# Pololu_Magnetic_Encoder.net
KiCad netlist of a schematic drawn in EAGLE
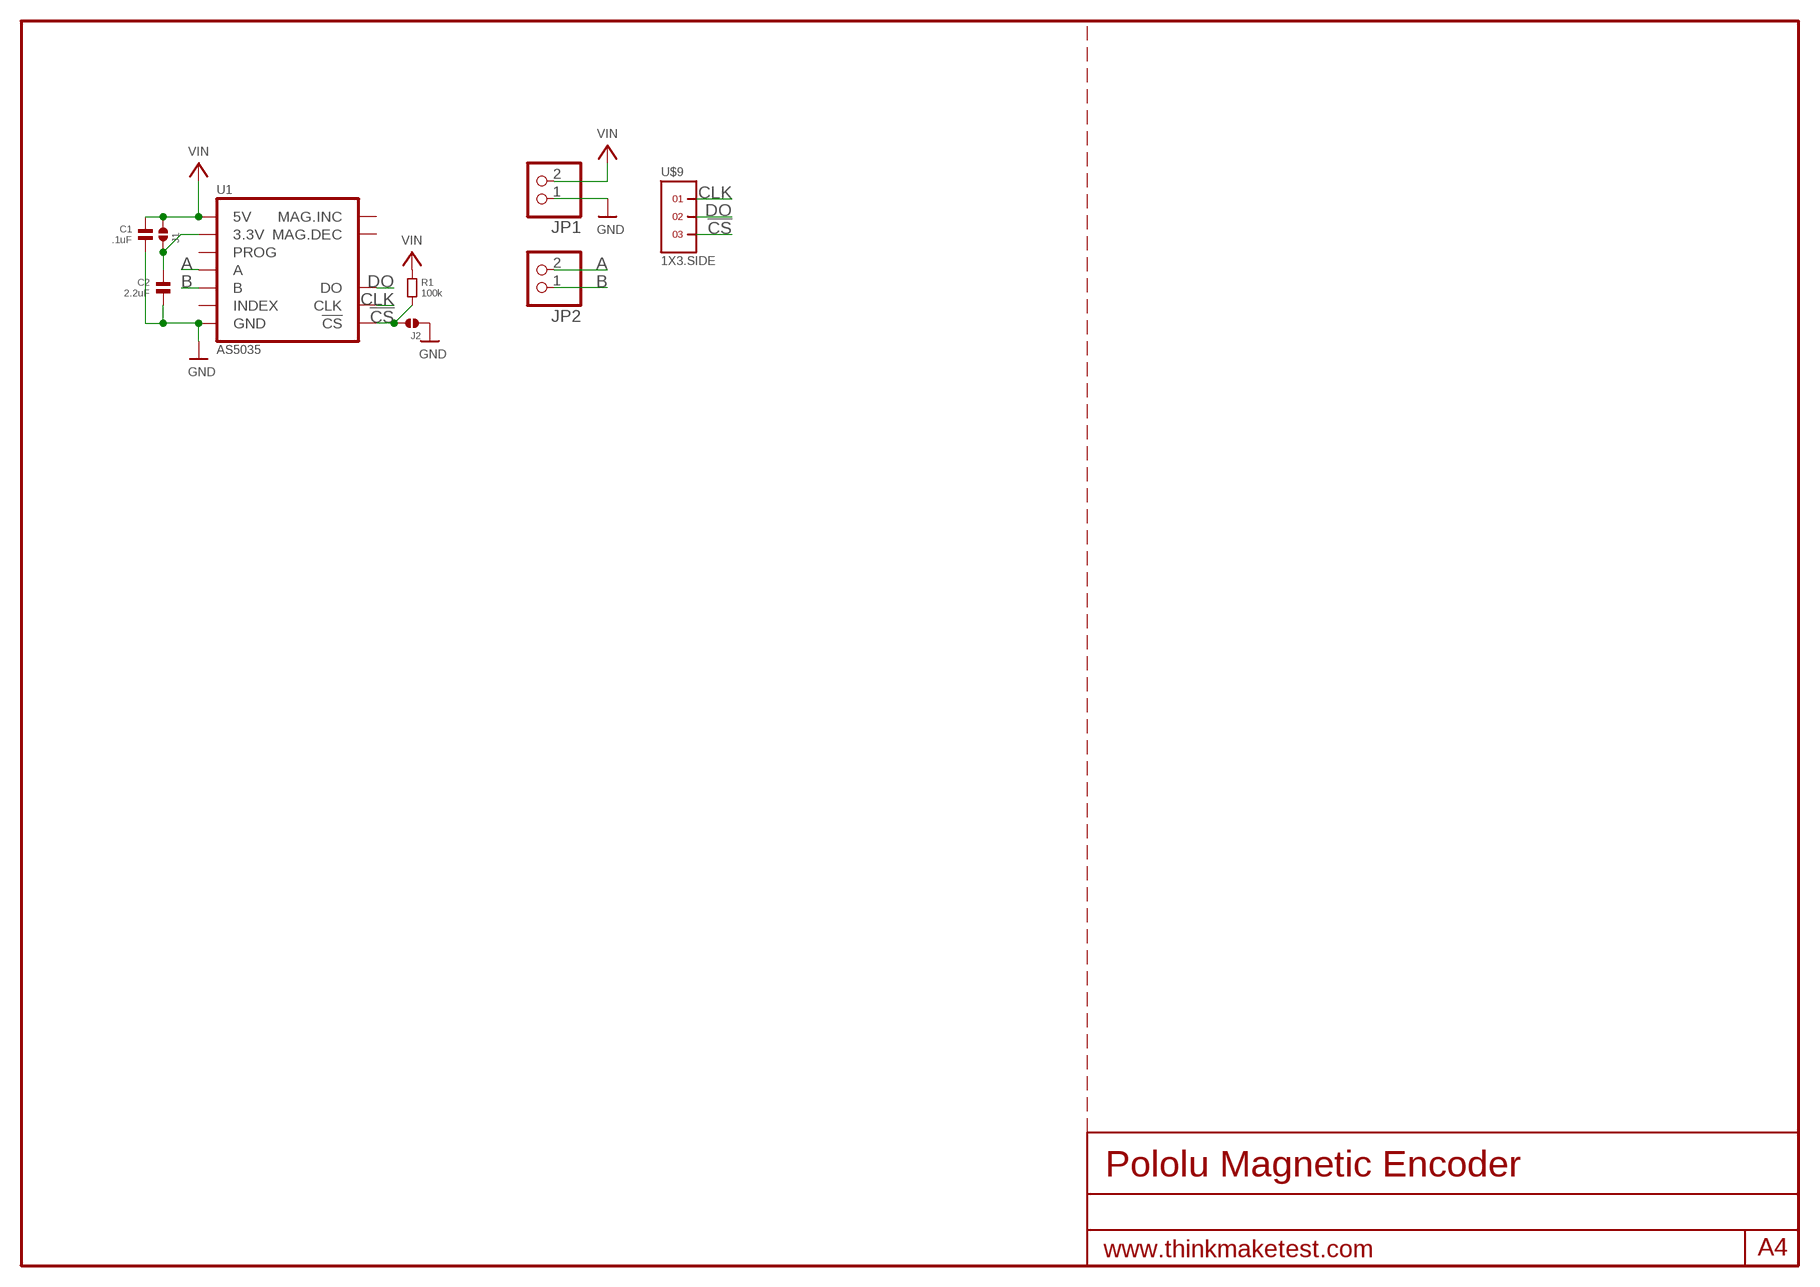
[diagram p0: schematic, sheet 1]

(export (version "E")
  (design (tool "Eeschema 10.0.6"))
  (components
    (comp (ref "C1")
      (value ".1uF")
      (footprint "eagle-import:0603")
      (libsource (lib "eagle-import") (part "CAPACITOR.0603"))
    )
    (comp (ref "C2")
      (value "2.2uF")
      (footprint "eagle-import:0603")
      (libsource (lib "eagle-import") (part "CAPACITOR.0603"))
    )
    (comp (ref "J1")
      (value "SOLDERJUMPER.2.LRG.PASTE")
      (footprint "eagle-import:2.LRG.PASTE")
      (libsource (lib "eagle-import") (part "SOLDERJUMPER.2.LRG.PASTE"))
    )
    (comp (ref "J2")
      (value "SOLDERJUMPER.2.LRG.PASTE")
      (footprint "eagle-import:2.LRG.PASTE")
      (libsource (lib "eagle-import") (part "SOLDERJUMPER.2.LRG.PASTE"))
    )
    (comp (ref "JP1")
      (value "HEADER-1X2ROUND")
      (footprint "eagle-import:1X02_ROUND")
      (libsource (lib "eagle-import") (part "HEADER-1X2ROUND"))
    )
    (comp (ref "JP2")
      (value "HEADER-1X2ROUND")
      (footprint "eagle-import:1X02_ROUND")
      (libsource (lib "eagle-import") (part "HEADER-1X2ROUND"))
    )
    (comp (ref "R1")
      (value "100k")
      (footprint "eagle-import:0603")
      (libsource (lib "eagle-import") (part "RESISTOR.0603"))
    )
    (comp (ref "U$9")
      (value "1X3.SIDE")
      (footprint "eagle-import:1X3.SIDE")
      (libsource (lib "eagle-import") (part "1X3.SIDE"))
    )
    (comp (ref "U1")
      (value "AS5035")
      (footprint "eagle-import:SSOP16")
      (libsource (lib "eagle-import") (part "AS5035"))
    )
  )
  (nets
    (net (code "1") (name "/A") (class "Default")
      (node (ref "JP2") (pin "2") (pinfunction "2_2") (pintype "passive"))
      (node (ref "U1") (pin "3") (pinfunction "A_3") (pintype "bidirectional"))
    )
    (net (code "2") (name "/B") (class "Default")
      (node (ref "JP2") (pin "1") (pinfunction "1_1") (pintype "passive"))
      (node (ref "U1") (pin "4") (pinfunction "B_4") (pintype "bidirectional"))
    )
    (net (code "3") (name "/CLK") (class "Default")
      (node (ref "U$9") (pin "1") (pinfunction "1_1") (pintype "bidirectional"))
      (node (ref "U1") (pin "10") (pinfunction "CLK_10") (pintype "bidirectional"))
    )
    (net (code "4") (name "/DO") (class "Default")
      (node (ref "U$9") (pin "2") (pinfunction "2_2") (pintype "bidirectional"))
      (node (ref "U1") (pin "9") (pinfunction "DO_9") (pintype "bidirectional"))
    )
    (net (code "5") (name "/~{CS}") (class "Default")
      (node (ref "J2") (pin "2") (pinfunction "2_2") (pintype "bidirectional"))
      (node (ref "R1") (pin "2") (pinfunction "2_2") (pintype "bidirectional"))
      (node (ref "U$9") (pin "3") (pinfunction "3_3") (pintype "bidirectional"))
      (node (ref "U1") (pin "11") (pinfunction "~{CS}_11") (pintype "bidirectional"))
    )
    (net (code "6") (name "GND") (class "Default")
      (node (ref "C1") (pin "2") (pinfunction "2_2") (pintype "bidirectional"))
      (node (ref "C2") (pin "2") (pinfunction "2_2") (pintype "bidirectional"))
      (node (ref "J2") (pin "1") (pinfunction "1_1") (pintype "bidirectional"))
      (node (ref "JP1") (pin "1") (pinfunction "1_1") (pintype "passive"))
      (node (ref "U1") (pin "7") (pinfunction "GND_7") (pintype "bidirectional"))
    )
    (net (code "7") (name "Net-(U1-3.3V)") (class "Default")
      (node (ref "C2") (pin "1") (pinfunction "1_1") (pintype "bidirectional"))
      (node (ref "J1") (pin "1") (pinfunction "1_1") (pintype "bidirectional"))
      (node (ref "U1") (pin "15") (pinfunction "3.3V_15") (pintype "bidirectional"))
    )
    (net (code "8") (name "VIN") (class "Default")
      (node (ref "C1") (pin "1") (pinfunction "1_1") (pintype "bidirectional"))
      (node (ref "J1") (pin "2") (pinfunction "2_2") (pintype "bidirectional"))
      (node (ref "JP1") (pin "2") (pinfunction "2_2") (pintype "passive"))
      (node (ref "R1") (pin "1") (pinfunction "1_1") (pintype "bidirectional"))
      (node (ref "U1") (pin "16") (pinfunction "5V_16") (pintype "bidirectional"))
    )
    (net (code "9") (name "unconnected-(U1-INDEX-Pad6)") (class "Default")
      (node (ref "U1") (pin "6") (pinfunction "INDEX_6") (pintype "bidirectional"))
    )
    (net (code "10") (name "unconnected-(U1-MAG.DEC-Pad2)") (class "Default")
      (node (ref "U1") (pin "2") (pinfunction "MAG.DEC_2") (pintype "bidirectional"))
    )
    (net (code "11") (name "unconnected-(U1-MAG.INC-Pad1)") (class "Default")
      (node (ref "U1") (pin "1") (pinfunction "MAG.INC_1") (pintype "bidirectional"))
    )
    (net (code "12") (name "unconnected-(U1-PROG-Pad8)") (class "Default")
      (node (ref "U1") (pin "8") (pinfunction "PROG_8") (pintype "bidirectional"))
    )
  )
)
